# panelolu_2_1.net
KiCad netlist of a schematic drawn in EAGLE
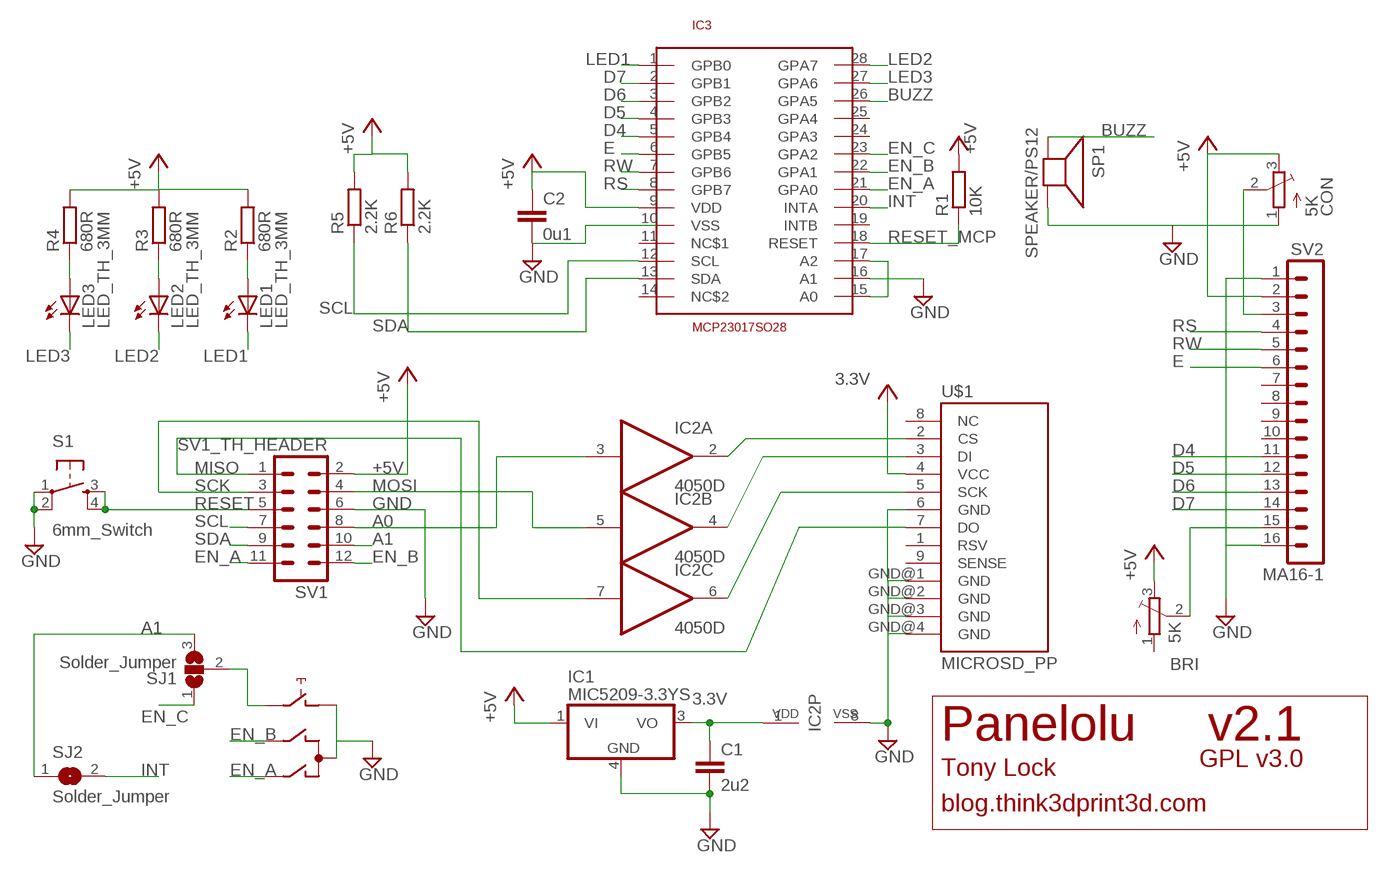
[diagram p0: schematic, sheet 1]

(export (version "E")
  (design (tool "Eeschema 10.0.6"))
  (components
    (comp (ref "BRI")
      (value "5K")
      (footprint "eagle-import:TC33X")
      (libsource (lib "eagle-import") (part "TRIMPOTTC33X"))
    )
    (comp (ref "C1")
      (value "2u2")
      (footprint "eagle-import:C1206K")
      (libsource (lib "eagle-import") (part "C-EUC1206K"))
    )
    (comp (ref "C2")
      (value "0u1")
      (footprint "eagle-import:C0805K")
      (libsource (lib "eagle-import") (part "resistor_C-EUC0805K"))
    )
    (comp (ref "CON")
      (value "5K")
      (footprint "eagle-import:TC33X")
      (libsource (lib "eagle-import") (part "TRIMPOTTC33X"))
    )
    (comp (ref "IC1")
      (value "MIC5209-3.3YS")
      (footprint "eagle-import:SOT223")
      (libsource (lib "eagle-import") (part "LM340?-MP05"))
    )
    (comp (ref "IC2")
      (value "4050D")
      (footprint "eagle-import:SO16")
      (libsource (lib "eagle-import") (part "4050D"))
    )
    (comp (ref "IC3")
      (value "MCP23017SO28")
      (footprint "eagle-import:SO28W")
      (libsource (lib "eagle-import") (part "MCP23017SO28"))
    )
    (comp (ref "LED1")
      (value "LED_TH_3MM")
      (footprint "eagle-import:LED3MM")
      (libsource (lib "eagle-import") (part "LED3MM"))
    )
    (comp (ref "LED2")
      (value "LED_TH_3MM")
      (footprint "eagle-import:LED3MM")
      (libsource (lib "eagle-import") (part "LED3MM"))
    )
    (comp (ref "LED3")
      (value "LED_TH_3MM")
      (footprint "eagle-import:LED3MM")
      (libsource (lib "eagle-import") (part "LED3MM"))
    )
    (comp (ref "R1")
      (value "10K")
      (footprint "eagle-import:M0805")
      (libsource (lib "eagle-import") (part "R-EU_M0805"))
    )
    (comp (ref "R2")
      (value "680R")
      (footprint "eagle-import:M0805")
      (libsource (lib "eagle-import") (part "R-EU_M0805"))
    )
    (comp (ref "R3")
      (value "680R")
      (footprint "eagle-import:M0805")
      (libsource (lib "eagle-import") (part "R-EU_M0805"))
    )
    (comp (ref "R4")
      (value "680R")
      (footprint "eagle-import:M0805")
      (libsource (lib "eagle-import") (part "R-EU_M0805"))
    )
    (comp (ref "R5")
      (value "2.2K")
      (footprint "eagle-import:M0805")
      (libsource (lib "eagle-import") (part "R-EU_M0805"))
    )
    (comp (ref "R6")
      (value "2.2K")
      (footprint "eagle-import:M0805")
      (libsource (lib "eagle-import") (part "R-EU_M0805"))
    )
    (comp (ref "S1")
      (value "6mm_Switch")
      (footprint "eagle-import:TACTILE-PTH")
      (libsource (lib "eagle-import") (part "TAC_SWITCHPTH"))
    )
    (comp (ref "SJ1")
      (value "Solder_Jumper")
      (footprint "eagle-import:SJ_2")
      (libsource (lib "eagle-import") (part "SJ2W"))
    )
    (comp (ref "SJ2")
      (value "Solder_Jumper")
      (footprint "eagle-import:SJ")
      (libsource (lib "eagle-import") (part "SJ"))
    )
    (comp (ref "SP1")
      (value "SPEAKER/PS12")
      (footprint "eagle-import:PS12")
      (libsource (lib "eagle-import") (part "SPEAKER/PS12"))
    )
    (comp (ref "SV1")
      (value "SV1_TH_HEADER")
      (footprint "eagle-import:MA06-2")
      (libsource (lib "eagle-import") (part "MA06-2"))
    )
    (comp (ref "SV2")
      (value "MA16-1")
      (footprint "eagle-import:MA16-1")
      (libsource (lib "eagle-import") (part "MA16-1"))
    )
    (comp (ref "SW1")
      (value "EC12E_SW")
      (footprint "eagle-import:ALPS_EC12E_SW")
      (fields (field (name "MPN") "EC12E2424407"))
      (libsource (lib "eagle-import") (part "EC12E_SW"))
    )
    (comp (ref "U$1")
      (value "MICROSD_PP")
      (footprint "eagle-import:MICROSD_PP")
      (libsource (lib "eagle-import") (part "MICROSD_PP"))
    )
  )
  (nets
    (net (code "1") (name "+5V") (class "Default")
      (node (ref "BRI") (pin "3") (pinfunction "E_3") (pintype "passive"))
      (node (ref "C2") (pin "1") (pinfunction "1_1") (pintype "passive"))
      (node (ref "CON") (pin "3") (pinfunction "E_3") (pintype "passive"))
      (node (ref "IC1") (pin "1") (pinfunction "VI_1") (pintype "input"))
      (node (ref "IC3") (pin "9") (pinfunction "VDD_9") (pintype "power_in"))
      (node (ref "R1") (pin "2") (pinfunction "2_2") (pintype "passive"))
      (node (ref "R2") (pin "2") (pinfunction "2_2") (pintype "passive"))
      (node (ref "R3") (pin "2") (pinfunction "2_2") (pintype "passive"))
      (node (ref "R4") (pin "2") (pinfunction "2_2") (pintype "passive"))
      (node (ref "R5") (pin "2") (pinfunction "2_2") (pintype "passive"))
      (node (ref "R6") (pin "2") (pinfunction "2_2") (pintype "passive"))
      (node (ref "SV1") (pin "2") (pinfunction "2_2") (pintype "passive"))
      (node (ref "SV2") (pin "2") (pinfunction "2_2") (pintype "passive"))
    )
    (net (code "2") (name "/A0") (class "Default")
      (node (ref "IC2") (pin "3") (pinfunction "I_3") (pintype "input"))
      (node (ref "SV1") (pin "8") (pinfunction "8_8") (pintype "passive"))
    )
    (net (code "3") (name "/A1") (class "Default")
      (node (ref "SJ1") (pin "3") (pinfunction "3_3") (pintype "passive"))
      (node (ref "SJ2") (pin "1") (pinfunction "1_1") (pintype "passive"))
      (node (ref "SV1") (pin "10") (pinfunction "10_10") (pintype "passive"))
    )
    (net (code "4") (name "/BUZZ") (class "Default")
      (node (ref "IC3") (pin "26") (pinfunction "GPA5_26") (pintype "bidirectional"))
      (node (ref "SP1") (pin "P$1") (pinfunction "+_P$1") (pintype "passive"))
    )
    (net (code "5") (name "/D4") (class "Default")
      (node (ref "IC3") (pin "5") (pinfunction "GPB4_5") (pintype "bidirectional"))
      (node (ref "SV2") (pin "11") (pinfunction "11_11") (pintype "passive"))
    )
    (net (code "6") (name "/D5") (class "Default")
      (node (ref "IC3") (pin "4") (pinfunction "GPB3_4") (pintype "bidirectional"))
      (node (ref "SV2") (pin "12") (pinfunction "12_12") (pintype "passive"))
    )
    (net (code "7") (name "/D6") (class "Default")
      (node (ref "IC3") (pin "3") (pinfunction "GPB2_3") (pintype "bidirectional"))
      (node (ref "SV2") (pin "13") (pinfunction "13_13") (pintype "passive"))
    )
    (net (code "8") (name "/D7") (class "Default")
      (node (ref "IC3") (pin "2") (pinfunction "GPB1_2") (pintype "bidirectional"))
      (node (ref "SV2") (pin "14") (pinfunction "14_14") (pintype "passive"))
    )
    (net (code "9") (name "/E") (class "Default")
      (node (ref "IC3") (pin "6") (pinfunction "GPB5_6") (pintype "bidirectional"))
      (node (ref "SV2") (pin "6") (pinfunction "6_6") (pintype "passive"))
    )
    (net (code "10") (name "/EN_A") (class "Default")
      (node (ref "IC3") (pin "21") (pinfunction "GPA0_21") (pintype "bidirectional"))
      (node (ref "SV1") (pin "11") (pinfunction "11_11") (pintype "passive"))
      (node (ref "SW1") (pin "A") (pinfunction "A_A") (pintype "passive"))
    )
    (net (code "11") (name "/EN_B") (class "Default")
      (node (ref "IC3") (pin "22") (pinfunction "GPA1_22") (pintype "bidirectional"))
      (node (ref "SV1") (pin "12") (pinfunction "12_12") (pintype "passive"))
      (node (ref "SW1") (pin "B") (pinfunction "B_B") (pintype "passive"))
    )
    (net (code "12") (name "/EN_C") (class "Default")
      (node (ref "IC3") (pin "23") (pinfunction "GPA2_23") (pintype "bidirectional"))
      (node (ref "SJ1") (pin "1") (pinfunction "1_1") (pintype "passive"))
    )
    (net (code "13") (name "/INT") (class "Default")
      (node (ref "IC3") (pin "20") (pinfunction "INTA_20") (pintype "output"))
      (node (ref "SJ2") (pin "2") (pinfunction "2_2") (pintype "passive"))
    )
    (net (code "14") (name "/LED1") (class "Default")
      (node (ref "IC3") (pin "1") (pinfunction "GPB0_1") (pintype "bidirectional"))
      (node (ref "LED1") (pin "K") (pinfunction "C_K") (pintype "passive"))
    )
    (net (code "15") (name "/LED2") (class "Default")
      (node (ref "IC3") (pin "28") (pinfunction "GPA7_28") (pintype "bidirectional"))
      (node (ref "LED2") (pin "K") (pinfunction "C_K") (pintype "passive"))
    )
    (net (code "16") (name "/LED3") (class "Default")
      (node (ref "IC3") (pin "27") (pinfunction "GPA6_27") (pintype "bidirectional"))
      (node (ref "LED3") (pin "K") (pinfunction "C_K") (pintype "passive"))
    )
    (net (code "17") (name "/MISO") (class "Default")
      (node (ref "SV1") (pin "1") (pinfunction "1_1") (pintype "passive"))
      (node (ref "U$1") (pin "7") (pinfunction "DO_7") (pintype "bidirectional"))
    )
    (net (code "18") (name "/MOSI") (class "Default")
      (node (ref "IC2") (pin "5") (pinfunction "I_5") (pintype "input"))
      (node (ref "SV1") (pin "4") (pinfunction "4_4") (pintype "passive"))
    )
    (net (code "19") (name "/RESET") (class "Default")
      (node (ref "S1") (pin "3") (pinfunction "3_3") (pintype "passive"))
      (node (ref "S1") (pin "4") (pinfunction "4_4") (pintype "passive"))
      (node (ref "SV1") (pin "5") (pinfunction "5_5") (pintype "passive"))
    )
    (net (code "20") (name "/RESET_MCP") (class "Default")
      (node (ref "IC3") (pin "18") (pinfunction "RESET_18") (pintype "output"))
      (node (ref "R1") (pin "1") (pinfunction "1_1") (pintype "passive"))
    )
    (net (code "21") (name "/RS") (class "Default")
      (node (ref "IC3") (pin "8") (pinfunction "GPB7_8") (pintype "bidirectional"))
      (node (ref "SV2") (pin "4") (pinfunction "4_4") (pintype "passive"))
    )
    (net (code "22") (name "/RW") (class "Default")
      (node (ref "IC3") (pin "7") (pinfunction "GPB6_7") (pintype "bidirectional"))
      (node (ref "SV2") (pin "5") (pinfunction "5_5") (pintype "passive"))
    )
    (net (code "23") (name "/SCK") (class "Default")
      (node (ref "IC2") (pin "7") (pinfunction "I_7") (pintype "input"))
      (node (ref "SV1") (pin "3") (pinfunction "3_3") (pintype "passive"))
    )
    (net (code "24") (name "/SCL") (class "Default")
      (node (ref "IC3") (pin "12") (pinfunction "SCL_12") (pintype "input"))
      (node (ref "R5") (pin "1") (pinfunction "1_1") (pintype "passive"))
      (node (ref "SV1") (pin "7") (pinfunction "7_7") (pintype "passive"))
    )
    (net (code "25") (name "/SDA") (class "Default")
      (node (ref "IC3") (pin "13") (pinfunction "SDA_13") (pintype "bidirectional"))
      (node (ref "R6") (pin "1") (pinfunction "1_1") (pintype "passive"))
      (node (ref "SV1") (pin "9") (pinfunction "9_9") (pintype "passive"))
    )
    (net (code "26") (name "3.3V") (class "Default")
      (node (ref "C1") (pin "1") (pinfunction "1_1") (pintype "passive"))
      (node (ref "IC1") (pin "3") (pinfunction "VO_3") (pintype "passive"))
      (node (ref "IC2") (pin "1") (pinfunction "VDD_1") (pintype "power_in"))
      (node (ref "U$1") (pin "4") (pinfunction "VCC_4") (pintype "bidirectional"))
    )
    (net (code "27") (name "GND") (class "Default")
      (node (ref "C1") (pin "2") (pinfunction "2_2") (pintype "passive"))
      (node (ref "C2") (pin "2") (pinfunction "2_2") (pintype "passive"))
      (node (ref "CON") (pin "1") (pinfunction "A_1") (pintype "passive"))
      (node (ref "IC1") (pin "4") (pinfunction "GND_4") (pintype "passive"))
      (node (ref "IC2") (pin "8") (pinfunction "VSS_8") (pintype "power_in"))
      (node (ref "IC3") (pin "10") (pinfunction "VSS_10") (pintype "power_in"))
      (node (ref "IC3") (pin "15") (pinfunction "A0_15") (pintype "input"))
      (node (ref "IC3") (pin "16") (pinfunction "A1_16") (pintype "input"))
      (node (ref "IC3") (pin "17") (pinfunction "A2_17") (pintype "input"))
      (node (ref "S1") (pin "1") (pinfunction "1_1") (pintype "passive"))
      (node (ref "S1") (pin "2") (pinfunction "2_2") (pintype "passive"))
      (node (ref "SP1") (pin "P$2") (pinfunction "-_P$2") (pintype "passive"))
      (node (ref "SV1") (pin "6") (pinfunction "6_6") (pintype "passive"))
      (node (ref "SV2") (pin "1") (pinfunction "1_1") (pintype "passive"))
      (node (ref "SV2") (pin "16") (pinfunction "16_16") (pintype "passive"))
      (node (ref "SW1") (pin "C") (pinfunction "C_C") (pintype "passive"))
      (node (ref "SW1") (pin "D") (pinfunction "1_D") (pintype "passive"))
      (node (ref "U$1") (pin "6") (pinfunction "GND_6") (pintype "bidirectional"))
      (node (ref "U$1") (pin "GND@1") (pinfunction "GND_GND@1") (pintype "bidirectional"))
      (node (ref "U$1") (pin "GND@2") (pinfunction "GND_GND@2") (pintype "bidirectional"))
      (node (ref "U$1") (pin "GND@3") (pinfunction "GND_GND@3") (pintype "bidirectional"))
      (node (ref "U$1") (pin "GND@4") (pinfunction "GND_GND@4") (pintype "bidirectional"))
    )
    (net (code "28") (name "Net-(BRI-S)") (class "Default")
      (node (ref "BRI") (pin "2") (pinfunction "S_2") (pintype "passive"))
      (node (ref "SV2") (pin "15") (pinfunction "15_15") (pintype "passive"))
    )
    (net (code "29") (name "Net-(CON-S)") (class "Default")
      (node (ref "CON") (pin "2") (pinfunction "S_2") (pintype "passive"))
      (node (ref "SV2") (pin "3") (pinfunction "3_3") (pintype "passive"))
    )
    (net (code "30") (name "Net-(IC2A-O)") (class "Default")
      (node (ref "IC2") (pin "2") (pinfunction "O_2") (pintype "output"))
      (node (ref "U$1") (pin "2") (pinfunction "CS_2") (pintype "bidirectional"))
    )
    (net (code "31") (name "Net-(IC2B-O)") (class "Default")
      (node (ref "IC2") (pin "4") (pinfunction "O_4") (pintype "output"))
      (node (ref "U$1") (pin "3") (pinfunction "DI_3") (pintype "bidirectional"))
    )
    (net (code "32") (name "Net-(IC2C-O)") (class "Default")
      (node (ref "IC2") (pin "6") (pinfunction "O_6") (pintype "output"))
      (node (ref "U$1") (pin "5") (pinfunction "SCK_5") (pintype "bidirectional"))
    )
    (net (code "33") (name "Net-(LED1-PadA)") (class "Default")
      (node (ref "LED1") (pin "A") (pinfunction "A_A") (pintype "passive"))
      (node (ref "R2") (pin "1") (pinfunction "1_1") (pintype "passive"))
    )
    (net (code "34") (name "Net-(LED2-PadA)") (class "Default")
      (node (ref "LED2") (pin "A") (pinfunction "A_A") (pintype "passive"))
      (node (ref "R3") (pin "1") (pinfunction "1_1") (pintype "passive"))
    )
    (net (code "35") (name "Net-(LED3-PadA)") (class "Default")
      (node (ref "LED3") (pin "A") (pinfunction "A_A") (pintype "passive"))
      (node (ref "R4") (pin "1") (pinfunction "1_1") (pintype "passive"))
    )
    (net (code "36") (name "Net-(SW1B-2)") (class "Default")
      (node (ref "SJ1") (pin "2") (pinfunction "2_2") (pintype "passive"))
      (node (ref "SW1") (pin "E") (pinfunction "2_E") (pintype "passive"))
    )
    (net (code "37") (name "unconnected-(BRI-A-Pad1)") (class "Default")
      (node (ref "BRI") (pin "1") (pinfunction "A_1") (pintype "passive"))
    )
    (net (code "38") (name "unconnected-(IC3-GPA3-Pad24)") (class "Default")
      (node (ref "IC3") (pin "24") (pinfunction "GPA3_24") (pintype "bidirectional"))
    )
    (net (code "39") (name "unconnected-(IC3-GPA4-Pad25)") (class "Default")
      (node (ref "IC3") (pin "25") (pinfunction "GPA4_25") (pintype "bidirectional"))
    )
    (net (code "40") (name "unconnected-(IC3-INTB-Pad19)") (class "Default")
      (node (ref "IC3") (pin "19") (pinfunction "INTB_19") (pintype "output"))
    )
    (net (code "41") (name "unconnected-(IC3-NC$1-Pad11)") (class "Default")
      (node (ref "IC3") (pin "11") (pinfunction "NC$1_11") (pintype "no_connect"))
    )
    (net (code "42") (name "unconnected-(IC3-NC$2-Pad14)") (class "Default")
      (node (ref "IC3") (pin "14") (pinfunction "NC$2_14") (pintype "no_connect"))
    )
    (net (code "43") (name "unconnected-(SV2-Pad7)") (class "Default")
      (node (ref "SV2") (pin "7") (pinfunction "7_7") (pintype "passive"))
    )
    (net (code "44") (name "unconnected-(SV2-Pad8)") (class "Default")
      (node (ref "SV2") (pin "8") (pinfunction "8_8") (pintype "passive"))
    )
    (net (code "45") (name "unconnected-(SV2-Pad9)") (class "Default")
      (node (ref "SV2") (pin "9") (pinfunction "9_9") (pintype "passive"))
    )
    (net (code "46") (name "unconnected-(SV2-Pad10)") (class "Default")
      (node (ref "SV2") (pin "10") (pinfunction "10_10") (pintype "passive"))
    )
    (net (code "47") (name "unconnected-(U$1-NC-Pad8)") (class "Default")
      (node (ref "U$1") (pin "8") (pinfunction "NC_8") (pintype "bidirectional"))
    )
    (net (code "48") (name "unconnected-(U$1-RSV-Pad1)") (class "Default")
      (node (ref "U$1") (pin "1") (pinfunction "RSV_1") (pintype "bidirectional"))
    )
    (net (code "49") (name "unconnected-(U$1-SENSE-Pad9)") (class "Default")
      (node (ref "U$1") (pin "9") (pinfunction "SENSE_9") (pintype "bidirectional"))
    )
  )
)
